# MS-PB16.net
KiCad netlist of a schematic drawn in EAGLE
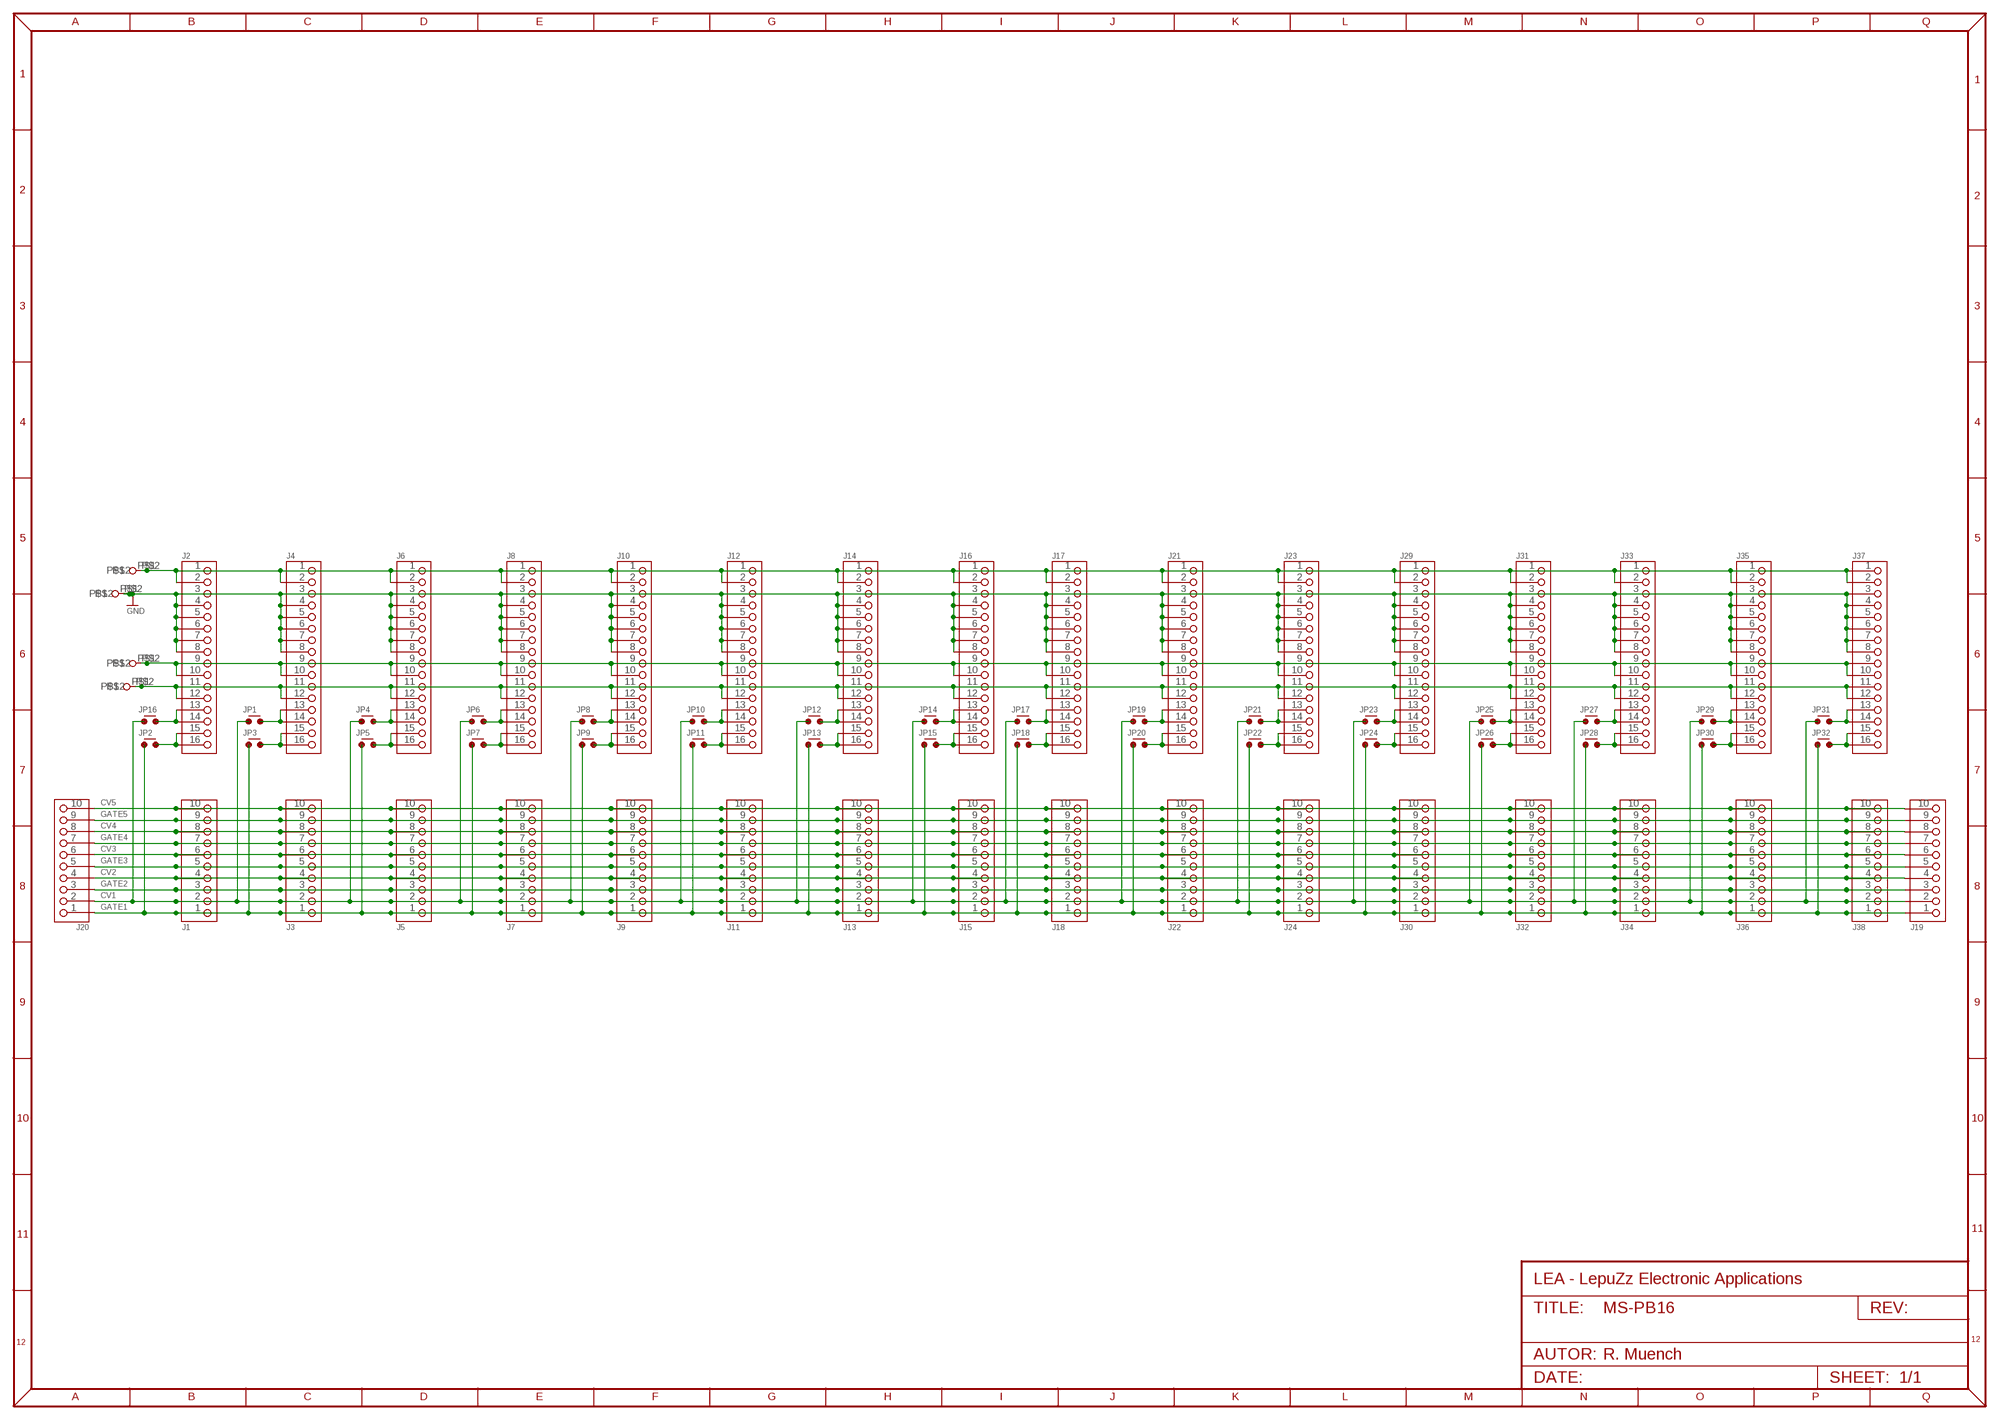
[diagram p0: schematic, sheet 1]

(export (version "E")
  (design (tool "Eeschema 10.0.6"))
  (components
    (comp (ref "J1")
      (value "CON10PD_S")
      (footprint "eagle-import:PD10S")
      (libsource (lib "eagle-import") (part "CON10PD_S"))
    )
    (comp (ref "J2")
      (value "CON16_PDS")
      (footprint "eagle-import:PD16S")
      (libsource (lib "eagle-import") (part "CON16_PDS"))
    )
    (comp (ref "J3")
      (value "CON10PD_S")
      (footprint "eagle-import:PD10S")
      (libsource (lib "eagle-import") (part "CON10PD_S"))
    )
    (comp (ref "J4")
      (value "CON16_PDS")
      (footprint "eagle-import:PD16S")
      (libsource (lib "eagle-import") (part "CON16_PDS"))
    )
    (comp (ref "J5")
      (value "CON10PD_S")
      (footprint "eagle-import:PD10S")
      (libsource (lib "eagle-import") (part "CON10PD_S"))
    )
    (comp (ref "J6")
      (value "CON16_PDS")
      (footprint "eagle-import:PD16S")
      (libsource (lib "eagle-import") (part "CON16_PDS"))
    )
    (comp (ref "J7")
      (value "CON10PD_S")
      (footprint "eagle-import:PD10S")
      (libsource (lib "eagle-import") (part "CON10PD_S"))
    )
    (comp (ref "J8")
      (value "CON16_PDS")
      (footprint "eagle-import:PD16S")
      (libsource (lib "eagle-import") (part "CON16_PDS"))
    )
    (comp (ref "J9")
      (value "CON10PD_S")
      (footprint "eagle-import:PD10S")
      (libsource (lib "eagle-import") (part "CON10PD_S"))
    )
    (comp (ref "J10")
      (value "CON16_PDS")
      (footprint "eagle-import:PD16S")
      (libsource (lib "eagle-import") (part "CON16_PDS"))
    )
    (comp (ref "J11")
      (value "CON10PD_S")
      (footprint "eagle-import:PD10S")
      (libsource (lib "eagle-import") (part "CON10PD_S"))
    )
    (comp (ref "J12")
      (value "CON16_PDS")
      (footprint "eagle-import:PD16S")
      (libsource (lib "eagle-import") (part "CON16_PDS"))
    )
    (comp (ref "J13")
      (value "CON10PD_S")
      (footprint "eagle-import:PD10S")
      (libsource (lib "eagle-import") (part "CON10PD_S"))
    )
    (comp (ref "J14")
      (value "CON16_PDS")
      (footprint "eagle-import:PD16S")
      (libsource (lib "eagle-import") (part "CON16_PDS"))
    )
    (comp (ref "J15")
      (value "CON10PD_S")
      (footprint "eagle-import:PD10S")
      (libsource (lib "eagle-import") (part "CON10PD_S"))
    )
    (comp (ref "J16")
      (value "CON16_PDS")
      (footprint "eagle-import:PD16S")
      (libsource (lib "eagle-import") (part "CON16_PDS"))
    )
    (comp (ref "J17")
      (value "CON16_PDS")
      (footprint "eagle-import:PD16S")
      (libsource (lib "eagle-import") (part "CON16_PDS"))
    )
    (comp (ref "J18")
      (value "CON10PD_S")
      (footprint "eagle-import:PD10S")
      (libsource (lib "eagle-import") (part "CON10PD_S"))
    )
    (comp (ref "J19")
      (value "CON10PD_S")
      (footprint "eagle-import:PD10S")
      (libsource (lib "eagle-import") (part "CON10PD_S"))
    )
    (comp (ref "J20")
      (value "CON10PD_S")
      (footprint "eagle-import:PD10S")
      (libsource (lib "eagle-import") (part "CON10PD_S"))
    )
    (comp (ref "J21")
      (value "CON16_PDS")
      (footprint "eagle-import:PD16S")
      (libsource (lib "eagle-import") (part "CON16_PDS"))
    )
    (comp (ref "J22")
      (value "CON10PD_S")
      (footprint "eagle-import:PD10S")
      (libsource (lib "eagle-import") (part "CON10PD_S"))
    )
    (comp (ref "J23")
      (value "CON16_PDS")
      (footprint "eagle-import:PD16S")
      (libsource (lib "eagle-import") (part "CON16_PDS"))
    )
    (comp (ref "J24")
      (value "CON10PD_S")
      (footprint "eagle-import:PD10S")
      (libsource (lib "eagle-import") (part "CON10PD_S"))
    )
    (comp (ref "J25")
      (value "FLACHSTECKER-6,35")
      (footprint "eagle-import:FLACHSTECKER-6,35")
      (libsource (lib "eagle-import") (part "FLACHSTECKER-6,35"))
    )
    (comp (ref "J26")
      (value "FLACHSTECKER-6,35")
      (footprint "eagle-import:FLACHSTECKER-6,35")
      (libsource (lib "eagle-import") (part "FLACHSTECKER-6,35"))
    )
    (comp (ref "J27")
      (value "FLACHSTECKER-6,35")
      (footprint "eagle-import:FLACHSTECKER-6,35")
      (libsource (lib "eagle-import") (part "FLACHSTECKER-6,35"))
    )
    (comp (ref "J28")
      (value "FLACHSTECKER-6,35")
      (footprint "eagle-import:FLACHSTECKER-6,35")
      (libsource (lib "eagle-import") (part "FLACHSTECKER-6,35"))
    )
    (comp (ref "J29")
      (value "CON16_PDS")
      (footprint "eagle-import:PD16S")
      (libsource (lib "eagle-import") (part "CON16_PDS"))
    )
    (comp (ref "J30")
      (value "CON10PD_S")
      (footprint "eagle-import:PD10S")
      (libsource (lib "eagle-import") (part "CON10PD_S"))
    )
    (comp (ref "J31")
      (value "CON16_PDS")
      (footprint "eagle-import:PD16S")
      (libsource (lib "eagle-import") (part "CON16_PDS"))
    )
    (comp (ref "J32")
      (value "CON10PD_S")
      (footprint "eagle-import:PD10S")
      (libsource (lib "eagle-import") (part "CON10PD_S"))
    )
    (comp (ref "J33")
      (value "CON16_PDS")
      (footprint "eagle-import:PD16S")
      (libsource (lib "eagle-import") (part "CON16_PDS"))
    )
    (comp (ref "J34")
      (value "CON10PD_S")
      (footprint "eagle-import:PD10S")
      (libsource (lib "eagle-import") (part "CON10PD_S"))
    )
    (comp (ref "J35")
      (value "CON16_PDS")
      (footprint "eagle-import:PD16S")
      (libsource (lib "eagle-import") (part "CON16_PDS"))
    )
    (comp (ref "J36")
      (value "CON10PD_S")
      (footprint "eagle-import:PD10S")
      (libsource (lib "eagle-import") (part "CON10PD_S"))
    )
    (comp (ref "J37")
      (value "CON16_PDS")
      (footprint "eagle-import:PD16S")
      (libsource (lib "eagle-import") (part "CON16_PDS"))
    )
    (comp (ref "J38")
      (value "CON10PD_S")
      (footprint "eagle-import:PD10S")
      (libsource (lib "eagle-import") (part "CON10PD_S"))
    )
    (comp (ref "JP1")
      (value "JUMP2J2")
      (footprint "eagle-import:JUMP2")
      (libsource (lib "eagle-import") (part "JUMP2J2"))
    )
    (comp (ref "JP2")
      (value "JUMP2J2")
      (footprint "eagle-import:JUMP2")
      (libsource (lib "eagle-import") (part "JUMP2J2"))
    )
    (comp (ref "JP3")
      (value "JUMP2J2")
      (footprint "eagle-import:JUMP2")
      (libsource (lib "eagle-import") (part "JUMP2J2"))
    )
    (comp (ref "JP4")
      (value "JUMP2J2")
      (footprint "eagle-import:JUMP2")
      (libsource (lib "eagle-import") (part "JUMP2J2"))
    )
    (comp (ref "JP5")
      (value "JUMP2J2")
      (footprint "eagle-import:JUMP2")
      (libsource (lib "eagle-import") (part "JUMP2J2"))
    )
    (comp (ref "JP6")
      (value "JUMP2J2")
      (footprint "eagle-import:JUMP2")
      (libsource (lib "eagle-import") (part "JUMP2J2"))
    )
    (comp (ref "JP7")
      (value "JUMP2J2")
      (footprint "eagle-import:JUMP2")
      (libsource (lib "eagle-import") (part "JUMP2J2"))
    )
    (comp (ref "JP8")
      (value "JUMP2J2")
      (footprint "eagle-import:JUMP2")
      (libsource (lib "eagle-import") (part "JUMP2J2"))
    )
    (comp (ref "JP9")
      (value "JUMP2J2")
      (footprint "eagle-import:JUMP2")
      (libsource (lib "eagle-import") (part "JUMP2J2"))
    )
    (comp (ref "JP10")
      (value "JUMP2J2")
      (footprint "eagle-import:JUMP2")
      (libsource (lib "eagle-import") (part "JUMP2J2"))
    )
    (comp (ref "JP11")
      (value "JUMP2J2")
      (footprint "eagle-import:JUMP2")
      (libsource (lib "eagle-import") (part "JUMP2J2"))
    )
    (comp (ref "JP12")
      (value "JUMP2J2")
      (footprint "eagle-import:JUMP2")
      (libsource (lib "eagle-import") (part "JUMP2J2"))
    )
    (comp (ref "JP13")
      (value "JUMP2J2")
      (footprint "eagle-import:JUMP2")
      (libsource (lib "eagle-import") (part "JUMP2J2"))
    )
    (comp (ref "JP14")
      (value "JUMP2J2")
      (footprint "eagle-import:JUMP2")
      (libsource (lib "eagle-import") (part "JUMP2J2"))
    )
    (comp (ref "JP15")
      (value "JUMP2J2")
      (footprint "eagle-import:JUMP2")
      (libsource (lib "eagle-import") (part "JUMP2J2"))
    )
    (comp (ref "JP16")
      (value "JUMP2J2")
      (footprint "eagle-import:JUMP2")
      (libsource (lib "eagle-import") (part "JUMP2J2"))
    )
    (comp (ref "JP17")
      (value "JUMP2J2")
      (footprint "eagle-import:JUMP2")
      (libsource (lib "eagle-import") (part "JUMP2J2"))
    )
    (comp (ref "JP18")
      (value "JUMP2J2")
      (footprint "eagle-import:JUMP2")
      (libsource (lib "eagle-import") (part "JUMP2J2"))
    )
    (comp (ref "JP19")
      (value "JUMP2J2")
      (footprint "eagle-import:JUMP2")
      (libsource (lib "eagle-import") (part "JUMP2J2"))
    )
    (comp (ref "JP20")
      (value "JUMP2J2")
      (footprint "eagle-import:JUMP2")
      (libsource (lib "eagle-import") (part "JUMP2J2"))
    )
    (comp (ref "JP21")
      (value "JUMP2J2")
      (footprint "eagle-import:JUMP2")
      (libsource (lib "eagle-import") (part "JUMP2J2"))
    )
    (comp (ref "JP22")
      (value "JUMP2J2")
      (footprint "eagle-import:JUMP2")
      (libsource (lib "eagle-import") (part "JUMP2J2"))
    )
    (comp (ref "JP23")
      (value "JUMP2J2")
      (footprint "eagle-import:JUMP2")
      (libsource (lib "eagle-import") (part "JUMP2J2"))
    )
    (comp (ref "JP24")
      (value "JUMP2J2")
      (footprint "eagle-import:JUMP2")
      (libsource (lib "eagle-import") (part "JUMP2J2"))
    )
    (comp (ref "JP25")
      (value "JUMP2J2")
      (footprint "eagle-import:JUMP2")
      (libsource (lib "eagle-import") (part "JUMP2J2"))
    )
    (comp (ref "JP26")
      (value "JUMP2J2")
      (footprint "eagle-import:JUMP2")
      (libsource (lib "eagle-import") (part "JUMP2J2"))
    )
    (comp (ref "JP27")
      (value "JUMP2J2")
      (footprint "eagle-import:JUMP2")
      (libsource (lib "eagle-import") (part "JUMP2J2"))
    )
    (comp (ref "JP28")
      (value "JUMP2J2")
      (footprint "eagle-import:JUMP2")
      (libsource (lib "eagle-import") (part "JUMP2J2"))
    )
    (comp (ref "JP29")
      (value "JUMP2J2")
      (footprint "eagle-import:JUMP2")
      (libsource (lib "eagle-import") (part "JUMP2J2"))
    )
    (comp (ref "JP30")
      (value "JUMP2J2")
      (footprint "eagle-import:JUMP2")
      (libsource (lib "eagle-import") (part "JUMP2J2"))
    )
    (comp (ref "JP31")
      (value "JUMP2J2")
      (footprint "eagle-import:JUMP2")
      (libsource (lib "eagle-import") (part "JUMP2J2"))
    )
    (comp (ref "JP32")
      (value "JUMP2J2")
      (footprint "eagle-import:JUMP2")
      (libsource (lib "eagle-import") (part "JUMP2J2"))
    )
  )
  (nets
    (net (code "1") (name "/+5V") (class "Default")
      (node (ref "J10") (pin "11") (pinfunction "11_11") (pintype "passive"))
      (node (ref "J10") (pin "12") (pinfunction "12_12") (pintype "passive"))
      (node (ref "J12") (pin "11") (pinfunction "11_11") (pintype "passive"))
      (node (ref "J12") (pin "12") (pinfunction "12_12") (pintype "passive"))
      (node (ref "J14") (pin "11") (pinfunction "11_11") (pintype "passive"))
      (node (ref "J14") (pin "12") (pinfunction "12_12") (pintype "passive"))
      (node (ref "J16") (pin "11") (pinfunction "11_11") (pintype "passive"))
      (node (ref "J16") (pin "12") (pinfunction "12_12") (pintype "passive"))
      (node (ref "J17") (pin "11") (pinfunction "11_11") (pintype "passive"))
      (node (ref "J17") (pin "12") (pinfunction "12_12") (pintype "passive"))
      (node (ref "J2") (pin "11") (pinfunction "11_11") (pintype "passive"))
      (node (ref "J2") (pin "12") (pinfunction "12_12") (pintype "passive"))
      (node (ref "J21") (pin "11") (pinfunction "11_11") (pintype "passive"))
      (node (ref "J21") (pin "12") (pinfunction "12_12") (pintype "passive"))
      (node (ref "J23") (pin "11") (pinfunction "11_11") (pintype "passive"))
      (node (ref "J23") (pin "12") (pinfunction "12_12") (pintype "passive"))
      (node (ref "J27") (pin "P$1") (pinfunction "P$1_P$1") (pintype "bidirectional"))
      (node (ref "J27") (pin "P$2") (pinfunction "P$2_P$2") (pintype "bidirectional"))
      (node (ref "J29") (pin "11") (pinfunction "11_11") (pintype "passive"))
      (node (ref "J29") (pin "12") (pinfunction "12_12") (pintype "passive"))
      (node (ref "J31") (pin "11") (pinfunction "11_11") (pintype "passive"))
      (node (ref "J31") (pin "12") (pinfunction "12_12") (pintype "passive"))
      (node (ref "J33") (pin "11") (pinfunction "11_11") (pintype "passive"))
      (node (ref "J33") (pin "12") (pinfunction "12_12") (pintype "passive"))
      (node (ref "J35") (pin "11") (pinfunction "11_11") (pintype "passive"))
      (node (ref "J35") (pin "12") (pinfunction "12_12") (pintype "passive"))
      (node (ref "J37") (pin "11") (pinfunction "11_11") (pintype "passive"))
      (node (ref "J37") (pin "12") (pinfunction "12_12") (pintype "passive"))
      (node (ref "J4") (pin "11") (pinfunction "11_11") (pintype "passive"))
      (node (ref "J4") (pin "12") (pinfunction "12_12") (pintype "passive"))
      (node (ref "J6") (pin "11") (pinfunction "11_11") (pintype "passive"))
      (node (ref "J6") (pin "12") (pinfunction "12_12") (pintype "passive"))
      (node (ref "J8") (pin "11") (pinfunction "11_11") (pintype "passive"))
      (node (ref "J8") (pin "12") (pinfunction "12_12") (pintype "passive"))
    )
    (net (code "2") (name "/+12V") (class "Default")
      (node (ref "J10") (pin "10") (pinfunction "10_10") (pintype "passive"))
      (node (ref "J10") (pin "9") (pinfunction "9_9") (pintype "passive"))
      (node (ref "J12") (pin "10") (pinfunction "10_10") (pintype "passive"))
      (node (ref "J12") (pin "9") (pinfunction "9_9") (pintype "passive"))
      (node (ref "J14") (pin "10") (pinfunction "10_10") (pintype "passive"))
      (node (ref "J14") (pin "9") (pinfunction "9_9") (pintype "passive"))
      (node (ref "J16") (pin "10") (pinfunction "10_10") (pintype "passive"))
      (node (ref "J16") (pin "9") (pinfunction "9_9") (pintype "passive"))
      (node (ref "J17") (pin "10") (pinfunction "10_10") (pintype "passive"))
      (node (ref "J17") (pin "9") (pinfunction "9_9") (pintype "passive"))
      (node (ref "J2") (pin "10") (pinfunction "10_10") (pintype "passive"))
      (node (ref "J2") (pin "9") (pinfunction "9_9") (pintype "passive"))
      (node (ref "J21") (pin "10") (pinfunction "10_10") (pintype "passive"))
      (node (ref "J21") (pin "9") (pinfunction "9_9") (pintype "passive"))
      (node (ref "J23") (pin "10") (pinfunction "10_10") (pintype "passive"))
      (node (ref "J23") (pin "9") (pinfunction "9_9") (pintype "passive"))
      (node (ref "J26") (pin "P$1") (pinfunction "P$1_P$1") (pintype "bidirectional"))
      (node (ref "J26") (pin "P$2") (pinfunction "P$2_P$2") (pintype "bidirectional"))
      (node (ref "J29") (pin "10") (pinfunction "10_10") (pintype "passive"))
      (node (ref "J29") (pin "9") (pinfunction "9_9") (pintype "passive"))
      (node (ref "J31") (pin "10") (pinfunction "10_10") (pintype "passive"))
      (node (ref "J31") (pin "9") (pinfunction "9_9") (pintype "passive"))
      (node (ref "J33") (pin "10") (pinfunction "10_10") (pintype "passive"))
      (node (ref "J33") (pin "9") (pinfunction "9_9") (pintype "passive"))
      (node (ref "J35") (pin "10") (pinfunction "10_10") (pintype "passive"))
      (node (ref "J35") (pin "9") (pinfunction "9_9") (pintype "passive"))
      (node (ref "J37") (pin "10") (pinfunction "10_10") (pintype "passive"))
      (node (ref "J37") (pin "9") (pinfunction "9_9") (pintype "passive"))
      (node (ref "J4") (pin "10") (pinfunction "10_10") (pintype "passive"))
      (node (ref "J4") (pin "9") (pinfunction "9_9") (pintype "passive"))
      (node (ref "J6") (pin "10") (pinfunction "10_10") (pintype "passive"))
      (node (ref "J6") (pin "9") (pinfunction "9_9") (pintype "passive"))
      (node (ref "J8") (pin "10") (pinfunction "10_10") (pintype "passive"))
      (node (ref "J8") (pin "9") (pinfunction "9_9") (pintype "passive"))
    )
    (net (code "3") (name "/-12V") (class "Default")
      (node (ref "J10") (pin "1") (pinfunction "1_1") (pintype "passive"))
      (node (ref "J10") (pin "2") (pinfunction "2_2") (pintype "passive"))
      (node (ref "J12") (pin "1") (pinfunction "1_1") (pintype "passive"))
      (node (ref "J12") (pin "2") (pinfunction "2_2") (pintype "passive"))
      (node (ref "J14") (pin "1") (pinfunction "1_1") (pintype "passive"))
      (node (ref "J14") (pin "2") (pinfunction "2_2") (pintype "passive"))
      (node (ref "J16") (pin "1") (pinfunction "1_1") (pintype "passive"))
      (node (ref "J16") (pin "2") (pinfunction "2_2") (pintype "passive"))
      (node (ref "J17") (pin "1") (pinfunction "1_1") (pintype "passive"))
      (node (ref "J17") (pin "2") (pinfunction "2_2") (pintype "passive"))
      (node (ref "J2") (pin "1") (pinfunction "1_1") (pintype "passive"))
      (node (ref "J2") (pin "2") (pinfunction "2_2") (pintype "passive"))
      (node (ref "J21") (pin "1") (pinfunction "1_1") (pintype "passive"))
      (node (ref "J21") (pin "2") (pinfunction "2_2") (pintype "passive"))
      (node (ref "J23") (pin "1") (pinfunction "1_1") (pintype "passive"))
      (node (ref "J23") (pin "2") (pinfunction "2_2") (pintype "passive"))
      (node (ref "J25") (pin "P$1") (pinfunction "P$1_P$1") (pintype "bidirectional"))
      (node (ref "J25") (pin "P$2") (pinfunction "P$2_P$2") (pintype "bidirectional"))
      (node (ref "J29") (pin "1") (pinfunction "1_1") (pintype "passive"))
      (node (ref "J29") (pin "2") (pinfunction "2_2") (pintype "passive"))
      (node (ref "J31") (pin "1") (pinfunction "1_1") (pintype "passive"))
      (node (ref "J31") (pin "2") (pinfunction "2_2") (pintype "passive"))
      (node (ref "J33") (pin "1") (pinfunction "1_1") (pintype "passive"))
      (node (ref "J33") (pin "2") (pinfunction "2_2") (pintype "passive"))
      (node (ref "J35") (pin "1") (pinfunction "1_1") (pintype "passive"))
      (node (ref "J35") (pin "2") (pinfunction "2_2") (pintype "passive"))
      (node (ref "J37") (pin "1") (pinfunction "1_1") (pintype "passive"))
      (node (ref "J37") (pin "2") (pinfunction "2_2") (pintype "passive"))
      (node (ref "J4") (pin "1") (pinfunction "1_1") (pintype "passive"))
      (node (ref "J4") (pin "2") (pinfunction "2_2") (pintype "passive"))
      (node (ref "J6") (pin "1") (pinfunction "1_1") (pintype "passive"))
      (node (ref "J6") (pin "2") (pinfunction "2_2") (pintype "passive"))
      (node (ref "J8") (pin "1") (pinfunction "1_1") (pintype "passive"))
      (node (ref "J8") (pin "2") (pinfunction "2_2") (pintype "passive"))
    )
    (net (code "4") (name "/CV1") (class "Default")
      (node (ref "J1") (pin "2") (pinfunction "2_2") (pintype "passive"))
      (node (ref "J11") (pin "2") (pinfunction "2_2") (pintype "passive"))
      (node (ref "J13") (pin "2") (pinfunction "2_2") (pintype "passive"))
      (node (ref "J15") (pin "2") (pinfunction "2_2") (pintype "passive"))
      (node (ref "J18") (pin "2") (pinfunction "2_2") (pintype "passive"))
      (node (ref "J19") (pin "2") (pinfunction "2_2") (pintype "passive"))
      (node (ref "J20") (pin "2") (pinfunction "2_2") (pintype "passive"))
      (node (ref "J22") (pin "2") (pinfunction "2_2") (pintype "passive"))
      (node (ref "J24") (pin "2") (pinfunction "2_2") (pintype "passive"))
      (node (ref "J3") (pin "2") (pinfunction "2_2") (pintype "passive"))
      (node (ref "J30") (pin "2") (pinfunction "2_2") (pintype "passive"))
      (node (ref "J32") (pin "2") (pinfunction "2_2") (pintype "passive"))
      (node (ref "J34") (pin "2") (pinfunction "2_2") (pintype "passive"))
      (node (ref "J36") (pin "2") (pinfunction "2_2") (pintype "passive"))
      (node (ref "J38") (pin "2") (pinfunction "2_2") (pintype "passive"))
      (node (ref "J5") (pin "2") (pinfunction "2_2") (pintype "passive"))
      (node (ref "J7") (pin "2") (pinfunction "2_2") (pintype "passive"))
      (node (ref "J9") (pin "2") (pinfunction "2_2") (pintype "passive"))
      (node (ref "JP1") (pin "1") (pinfunction "1_1") (pintype "passive"))
      (node (ref "JP10") (pin "1") (pinfunction "1_1") (pintype "passive"))
      (node (ref "JP12") (pin "1") (pinfunction "1_1") (pintype "passive"))
      (node (ref "JP14") (pin "1") (pinfunction "1_1") (pintype "passive"))
      (node (ref "JP16") (pin "1") (pinfunction "1_1") (pintype "passive"))
      (node (ref "JP17") (pin "1") (pinfunction "1_1") (pintype "passive"))
      (node (ref "JP19") (pin "1") (pinfunction "1_1") (pintype "passive"))
      (node (ref "JP21") (pin "1") (pinfunction "1_1") (pintype "passive"))
      (node (ref "JP23") (pin "1") (pinfunction "1_1") (pintype "passive"))
      (node (ref "JP25") (pin "1") (pinfunction "1_1") (pintype "passive"))
      (node (ref "JP27") (pin "1") (pinfunction "1_1") (pintype "passive"))
      (node (ref "JP29") (pin "1") (pinfunction "1_1") (pintype "passive"))
      (node (ref "JP31") (pin "1") (pinfunction "1_1") (pintype "passive"))
      (node (ref "JP4") (pin "1") (pinfunction "1_1") (pintype "passive"))
      (node (ref "JP6") (pin "1") (pinfunction "1_1") (pintype "passive"))
      (node (ref "JP8") (pin "1") (pinfunction "1_1") (pintype "passive"))
    )
    (net (code "5") (name "/CV2") (class "Default")
      (node (ref "J1") (pin "4") (pinfunction "4_4") (pintype "passive"))
      (node (ref "J11") (pin "4") (pinfunction "4_4") (pintype "passive"))
      (node (ref "J13") (pin "4") (pinfunction "4_4") (pintype "passive"))
      (node (ref "J15") (pin "4") (pinfunction "4_4") (pintype "passive"))
      (node (ref "J18") (pin "4") (pinfunction "4_4") (pintype "passive"))
      (node (ref "J19") (pin "4") (pinfunction "4_4") (pintype "passive"))
      (node (ref "J20") (pin "4") (pinfunction "4_4") (pintype "passive"))
      (node (ref "J22") (pin "4") (pinfunction "4_4") (pintype "passive"))
      (node (ref "J24") (pin "4") (pinfunction "4_4") (pintype "passive"))
      (node (ref "J3") (pin "4") (pinfunction "4_4") (pintype "passive"))
      (node (ref "J30") (pin "4") (pinfunction "4_4") (pintype "passive"))
      (node (ref "J32") (pin "4") (pinfunction "4_4") (pintype "passive"))
      (node (ref "J34") (pin "4") (pinfunction "4_4") (pintype "passive"))
      (node (ref "J36") (pin "4") (pinfunction "4_4") (pintype "passive"))
      (node (ref "J38") (pin "4") (pinfunction "4_4") (pintype "passive"))
      (node (ref "J5") (pin "4") (pinfunction "4_4") (pintype "passive"))
      (node (ref "J7") (pin "4") (pinfunction "4_4") (pintype "passive"))
      (node (ref "J9") (pin "4") (pinfunction "4_4") (pintype "passive"))
    )
    (net (code "6") (name "/CV3") (class "Default")
      (node (ref "J1") (pin "6") (pinfunction "6_6") (pintype "passive"))
      (node (ref "J11") (pin "6") (pinfunction "6_6") (pintype "passive"))
      (node (ref "J13") (pin "6") (pinfunction "6_6") (pintype "passive"))
      (node (ref "J15") (pin "6") (pinfunction "6_6") (pintype "passive"))
      (node (ref "J18") (pin "6") (pinfunction "6_6") (pintype "passive"))
      (node (ref "J19") (pin "6") (pinfunction "6_6") (pintype "passive"))
      (node (ref "J20") (pin "6") (pinfunction "6_6") (pintype "passive"))
      (node (ref "J22") (pin "6") (pinfunction "6_6") (pintype "passive"))
      (node (ref "J24") (pin "6") (pinfunction "6_6") (pintype "passive"))
      (node (ref "J3") (pin "6") (pinfunction "6_6") (pintype "passive"))
      (node (ref "J30") (pin "6") (pinfunction "6_6") (pintype "passive"))
      (node (ref "J32") (pin "6") (pinfunction "6_6") (pintype "passive"))
      (node (ref "J34") (pin "6") (pinfunction "6_6") (pintype "passive"))
      (node (ref "J36") (pin "6") (pinfunction "6_6") (pintype "passive"))
      (node (ref "J38") (pin "6") (pinfunction "6_6") (pintype "passive"))
      (node (ref "J5") (pin "6") (pinfunction "6_6") (pintype "passive"))
      (node (ref "J7") (pin "6") (pinfunction "6_6") (pintype "passive"))
      (node (ref "J9") (pin "6") (pinfunction "6_6") (pintype "passive"))
    )
    (net (code "7") (name "/CV4") (class "Default")
      (node (ref "J1") (pin "8") (pinfunction "8_8") (pintype "passive"))
      (node (ref "J11") (pin "8") (pinfunction "8_8") (pintype "passive"))
      (node (ref "J13") (pin "8") (pinfunction "8_8") (pintype "passive"))
      (node (ref "J15") (pin "8") (pinfunction "8_8") (pintype "passive"))
      (node (ref "J18") (pin "8") (pinfunction "8_8") (pintype "passive"))
      (node (ref "J19") (pin "8") (pinfunction "8_8") (pintype "passive"))
      (node (ref "J20") (pin "8") (pinfunction "8_8") (pintype "passive"))
      (node (ref "J22") (pin "8") (pinfunction "8_8") (pintype "passive"))
      (node (ref "J24") (pin "8") (pinfunction "8_8") (pintype "passive"))
      (node (ref "J3") (pin "8") (pinfunction "8_8") (pintype "passive"))
      (node (ref "J30") (pin "8") (pinfunction "8_8") (pintype "passive"))
      (node (ref "J32") (pin "8") (pinfunction "8_8") (pintype "passive"))
      (node (ref "J34") (pin "8") (pinfunction "8_8") (pintype "passive"))
      (node (ref "J36") (pin "8") (pinfunction "8_8") (pintype "passive"))
      (node (ref "J38") (pin "8") (pinfunction "8_8") (pintype "passive"))
      (node (ref "J5") (pin "8") (pinfunction "8_8") (pintype "passive"))
      (node (ref "J7") (pin "8") (pinfunction "8_8") (pintype "passive"))
      (node (ref "J9") (pin "8") (pinfunction "8_8") (pintype "passive"))
    )
    (net (code "8") (name "/CV5") (class "Default")
      (node (ref "J1") (pin "10") (pinfunction "10_10") (pintype "passive"))
      (node (ref "J11") (pin "10") (pinfunction "10_10") (pintype "passive"))
      (node (ref "J13") (pin "10") (pinfunction "10_10") (pintype "passive"))
      (node (ref "J15") (pin "10") (pinfunction "10_10") (pintype "passive"))
      (node (ref "J18") (pin "10") (pinfunction "10_10") (pintype "passive"))
      (node (ref "J19") (pin "10") (pinfunction "10_10") (pintype "passive"))
      (node (ref "J20") (pin "10") (pinfunction "10_10") (pintype "passive"))
      (node (ref "J22") (pin "10") (pinfunction "10_10") (pintype "passive"))
      (node (ref "J24") (pin "10") (pinfunction "10_10") (pintype "passive"))
      (node (ref "J3") (pin "10") (pinfunction "10_10") (pintype "passive"))
      (node (ref "J30") (pin "10") (pinfunction "10_10") (pintype "passive"))
      (node (ref "J32") (pin "10") (pinfunction "10_10") (pintype "passive"))
      (node (ref "J34") (pin "10") (pinfunction "10_10") (pintype "passive"))
      (node (ref "J36") (pin "10") (pinfunction "10_10") (pintype "passive"))
      (node (ref "J38") (pin "10") (pinfunction "10_10") (pintype "passive"))
      (node (ref "J5") (pin "10") (pinfunction "10_10") (pintype "passive"))
      (node (ref "J7") (pin "10") (pinfunction "10_10") (pintype "passive"))
      (node (ref "J9") (pin "10") (pinfunction "10_10") (pintype "passive"))
    )
    (net (code "9") (name "/GATE1") (class "Default")
      (node (ref "J1") (pin "1") (pinfunction "1_1") (pintype "passive"))
      (node (ref "J11") (pin "1") (pinfunction "1_1") (pintype "passive"))
      (node (ref "J13") (pin "1") (pinfunction "1_1") (pintype "passive"))
      (node (ref "J15") (pin "1") (pinfunction "1_1") (pintype "passive"))
      (node (ref "J18") (pin "1") (pinfunction "1_1") (pintype "passive"))
      (node (ref "J19") (pin "1") (pinfunction "1_1") (pintype "passive"))
      (node (ref "J20") (pin "1") (pinfunction "1_1") (pintype "passive"))
      (node (ref "J22") (pin "1") (pinfunction "1_1") (pintype "passive"))
      (node (ref "J24") (pin "1") (pinfunction "1_1") (pintype "passive"))
      (node (ref "J3") (pin "1") (pinfunction "1_1") (pintype "passive"))
      (node (ref "J30") (pin "1") (pinfunction "1_1") (pintype "passive"))
      (node (ref "J32") (pin "1") (pinfunction "1_1") (pintype "passive"))
      (node (ref "J34") (pin "1") (pinfunction "1_1") (pintype "passive"))
      (node (ref "J36") (pin "1") (pinfunction "1_1") (pintype "passive"))
      (node (ref "J38") (pin "1") (pinfunction "1_1") (pintype "passive"))
      (node (ref "J5") (pin "1") (pinfunction "1_1") (pintype "passive"))
      (node (ref "J7") (pin "1") (pinfunction "1_1") (pintype "passive"))
      (node (ref "J9") (pin "1") (pinfunction "1_1") (pintype "passive"))
      (node (ref "JP11") (pin "1") (pinfunction "1_1") (pintype "passive"))
      (node (ref "JP13") (pin "1") (pinfunction "1_1") (pintype "passive"))
      (node (ref "JP15") (pin "1") (pinfunction "1_1") (pintype "passive"))
      (node (ref "JP18") (pin "1") (pinfunction "1_1") (pintype "passive"))
      (node (ref "JP2") (pin "1") (pinfunction "1_1") (pintype "passive"))
      (node (ref "JP20") (pin "1") (pinfunction "1_1") (pintype "passive"))
      (node (ref "JP22") (pin "1") (pinfunction "1_1") (pintype "passive"))
      (node (ref "JP24") (pin "1") (pinfunction "1_1") (pintype "passive"))
      (node (ref "JP26") (pin "1") (pinfunction "1_1") (pintype "passive"))
      (node (ref "JP28") (pin "1") (pinfunction "1_1") (pintype "passive"))
      (node (ref "JP3") (pin "1") (pinfunction "1_1") (pintype "passive"))
      (node (ref "JP30") (pin "1") (pinfunction "1_1") (pintype "passive"))
      (node (ref "JP32") (pin "1") (pinfunction "1_1") (pintype "passive"))
      (node (ref "JP5") (pin "1") (pinfunction "1_1") (pintype "passive"))
      (node (ref "JP7") (pin "1") (pinfunction "1_1") (pintype "passive"))
      (node (ref "JP9") (pin "1") (pinfunction "1_1") (pintype "passive"))
    )
    (net (code "10") (name "/GATE2") (class "Default")
      (node (ref "J1") (pin "3") (pinfunction "3_3") (pintype "passive"))
      (node (ref "J11") (pin "3") (pinfunction "3_3") (pintype "passive"))
      (node (ref "J13") (pin "3") (pinfunction "3_3") (pintype "passive"))
      (node (ref "J15") (pin "3") (pinfunction "3_3") (pintype "passive"))
      (node (ref "J18") (pin "3") (pinfunction "3_3") (pintype "passive"))
      (node (ref "J19") (pin "3") (pinfunction "3_3") (pintype "passive"))
      (node (ref "J20") (pin "3") (pinfunction "3_3") (pintype "passive"))
      (node (ref "J22") (pin "3") (pinfunction "3_3") (pintype "passive"))
      (node (ref "J24") (pin "3") (pinfunction "3_3") (pintype "passive"))
      (node (ref "J3") (pin "3") (pinfunction "3_3") (pintype "passive"))
      (node (ref "J30") (pin "3") (pinfunction "3_3") (pintype "passive"))
      (node (ref "J32") (pin "3") (pinfunction "3_3") (pintype "passive"))
      (node (ref "J34") (pin "3") (pinfunction "3_3") (pintype "passive"))
      (node (ref "J36") (pin "3") (pinfunction "3_3") (pintype "passive"))
      (node (ref "J38") (pin "3") (pinfunction "3_3") (pintype "passive"))
      (node (ref "J5") (pin "3") (pinfunction "3_3") (pintype "passive"))
      (node (ref "J7") (pin "3") (pinfunction "3_3") (pintype "passive"))
      (node (ref "J9") (pin "3") (pinfunction "3_3") (pintype "passive"))
    )
    (net (code "11") (name "/GATE3") (class "Default")
      (node (ref "J1") (pin "5") (pinfunction "5_5") (pintype "passive"))
      (node (ref "J11") (pin "5") (pinfunction "5_5") (pintype "passive"))
      (node (ref "J13") (pin "5") (pinfunction "5_5") (pintype "passive"))
      (node (ref "J15") (pin "5") (pinfunction "5_5") (pintype "passive"))
      (node (ref "J18") (pin "5") (pinfunction "5_5") (pintype "passive"))
      (node (ref "J19") (pin "5") (pinfunction "5_5") (pintype "passive"))
      (node (ref "J20") (pin "5") (pinfunction "5_5") (pintype "passive"))
      (node (ref "J22") (pin "5") (pinfunction "5_5") (pintype "passive"))
      (node (ref "J24") (pin "5") (pinfunction "5_5") (pintype "passive"))
      (node (ref "J3") (pin "5") (pinfunction "5_5") (pintype "passive"))
      (node (ref "J30") (pin "5") (pinfunction "5_5") (pintype "passive"))
      (node (ref "J32") (pin "5") (pinfunction "5_5") (pintype "passive"))
      (node (ref "J34") (pin "5") (pinfunction "5_5") (pintype "passive"))
      (node (ref "J36") (pin "5") (pinfunction "5_5") (pintype "passive"))
      (node (ref "J38") (pin "5") (pinfunction "5_5") (pintype "passive"))
      (node (ref "J5") (pin "5") (pinfunction "5_5") (pintype "passive"))
      (node (ref "J7") (pin "5") (pinfunction "5_5") (pintype "passive"))
      (node (ref "J9") (pin "5") (pinfunction "5_5") (pintype "passive"))
    )
    (net (code "12") (name "/GATE4") (class "Default")
      (node (ref "J1") (pin "7") (pinfunction "7_7") (pintype "passive"))
      (node (ref "J11") (pin "7") (pinfunction "7_7") (pintype "passive"))
      (node (ref "J13") (pin "7") (pinfunction "7_7") (pintype "passive"))
      (node (ref "J15") (pin "7") (pinfunction "7_7") (pintype "passive"))
      (node (ref "J18") (pin "7") (pinfunction "7_7") (pintype "passive"))
      (node (ref "J19") (pin "7") (pinfunction "7_7") (pintype "passive"))
      (node (ref "J20") (pin "7") (pinfunction "7_7") (pintype "passive"))
      (node (ref "J22") (pin "7") (pinfunction "7_7") (pintype "passive"))
      (node (ref "J24") (pin "7") (pinfunction "7_7") (pintype "passive"))
      (node (ref "J3") (pin "7") (pinfunction "7_7") (pintype "passive"))
      (node (ref "J30") (pin "7") (pinfunction "7_7") (pintype "passive"))
      (node (ref "J32") (pin "7") (pinfunction "7_7") (pintype "passive"))
      (node (ref "J34") (pin "7") (pinfunction "7_7") (pintype "passive"))
      (node (ref "J36") (pin "7") (pinfunction "7_7") (pintype "passive"))
      (node (ref "J38") (pin "7") (pinfunction "7_7") (pintype "passive"))
      (node (ref "J5") (pin "7") (pinfunction "7_7") (pintype "passive"))
      (node (ref "J7") (pin "7") (pinfunction "7_7") (pintype "passive"))
      (node (ref "J9") (pin "7") (pinfunction "7_7") (pintype "passive"))
    )
    (net (code "13") (name "/GATE5") (class "Default")
      (node (ref "J1") (pin "9") (pinfunction "9_9") (pintype "passive"))
      (node (ref "J11") (pin "9") (pinfunction "9_9") (pintype "passive"))
      (node (ref "J13") (pin "9") (pinfunction "9_9") (pintype "passive"))
      (node (ref "J15") (pin "9") (pinfunction "9_9") (pintype "passive"))
      (node (ref "J18") (pin "9") (pinfunction "9_9") (pintype "passive"))
      (node (ref "J19") (pin "9") (pinfunction "9_9") (pintype "passive"))
      (node (ref "J20") (pin "9") (pinfunction "9_9") (pintype "passive"))
      (node (ref "J22") (pin "9") (pinfunction "9_9") (pintype "passive"))
      (node (ref "J24") (pin "9") (pinfunction "9_9") (pintype "passive"))
      (node (ref "J3") (pin "9") (pinfunction "9_9") (pintype "passive"))
      (node (ref "J30") (pin "9") (pinfunction "9_9") (pintype "passive"))
      (node (ref "J32") (pin "9") (pinfunction "9_9") (pintype "passive"))
      (node (ref "J34") (pin "9") (pinfunction "9_9") (pintype "passive"))
      (node (ref "J36") (pin "9") (pinfunction "9_9") (pintype "passive"))
      (node (ref "J38") (pin "9") (pinfunction "9_9") (pintype "passive"))
      (node (ref "J5") (pin "9") (pinfunction "9_9") (pintype "passive"))
      (node (ref "J7") (pin "9") (pinfunction "9_9") (pintype "passive"))
      (node (ref "J9") (pin "9") (pinfunction "9_9") (pintype "passive"))
    )
    (net (code "14") (name "GND") (class "Default")
      (node (ref "J10") (pin "3") (pinfunction "3_3") (pintype "passive"))
      (node (ref "J10") (pin "4") (pinfunction "4_4") (pintype "passive"))
      (node (ref "J10") (pin "5") (pinfunction "5_5") (pintype "passive"))
      (node (ref "J10") (pin "6") (pinfunction "6_6") (pintype "passive"))
      (node (ref "J10") (pin "7") (pinfunction "7_7") (pintype "passive"))
      (node (ref "J10") (pin "8") (pinfunction "8_8") (pintype "passive"))
      (node (ref "J12") (pin "3") (pinfunction "3_3") (pintype "passive"))
      (node (ref "J12") (pin "4") (pinfunction "4_4") (pintype "passive"))
      (node (ref "J12") (pin "5") (pinfunction "5_5") (pintype "passive"))
      (node (ref "J12") (pin "6") (pinfunction "6_6") (pintype "passive"))
      (node (ref "J12") (pin "7") (pinfunction "7_7") (pintype "passive"))
      (node (ref "J12") (pin "8") (pinfunction "8_8") (pintype "passive"))
      (node (ref "J14") (pin "3") (pinfunction "3_3") (pintype "passive"))
      (node (ref "J14") (pin "4") (pinfunction "4_4") (pintype "passive"))
      (node (ref "J14") (pin "5") (pinfunction "5_5") (pintype "passive"))
      (node (ref "J14") (pin "6") (pinfunction "6_6") (pintype "passive"))
      (node (ref "J14") (pin "7") (pinfunction "7_7") (pintype "passive"))
      (node (ref "J14") (pin "8") (pinfunction "8_8") (pintype "passive"))
      (node (ref "J16") (pin "3") (pinfunction "3_3") (pintype "passive"))
      (node (ref "J16") (pin "4") (pinfunction "4_4") (pintype "passive"))
      (node (ref "J16") (pin "5") (pinfunction "5_5") (pintype "passive"))
      (node (ref "J16") (pin "6") (pinfunction "6_6") (pintype "passive"))
      (node (ref "J16") (pin "7") (pinfunction "7_7") (pintype "passive"))
      (node (ref "J16") (pin "8") (pinfunction "8_8") (pintype "passive"))
      (node (ref "J17") (pin "3") (pinfunction "3_3") (pintype "passive"))
      (node (ref "J17") (pin "4") (pinfunction "4_4") (pintype "passive"))
      (node (ref "J17") (pin "5") (pinfunction "5_5") (pintype "passive"))
      (node (ref "J17") (pin "6") (pinfunction "6_6") (pintype "passive"))
      (node (ref "J17") (pin "7") (pinfunction "7_7") (pintype "passive"))
      (node (ref "J17") (pin "8") (pinfunction "8_8") (pintype "passive"))
      (node (ref "J2") (pin "3") (pinfunction "3_3") (pintype "passive"))
      (node (ref "J2") (pin "4") (pinfunction "4_4") (pintype "passive"))
      (node (ref "J2") (pin "5") (pinfunction "5_5") (pintype "passive"))
      (node (ref "J2") (pin "6") (pinfunction "6_6") (pintype "passive"))
      (node (ref "J2") (pin "7") (pinfunction "7_7") (pintype "passive"))
      (node (ref "J2") (pin "8") (pinfunction "8_8") (pintype "passive"))
      (node (ref "J21") (pin "3") (pinfunction "3_3") (pintype "passive"))
      (node (ref "J21") (pin "4") (pinfunction "4_4") (pintype "passive"))
      (node (ref "J21") (pin "5") (pinfunction "5_5") (pintype "passive"))
      (node (ref "J21") (pin "6") (pinfunction "6_6") (pintype "passive"))
      (node (ref "J21") (pin "7") (pinfunction "7_7") (pintype "passive"))
      (node (ref "J21") (pin "8") (pinfunction "8_8") (pintype "passive"))
      (node (ref "J23") (pin "3") (pinfunction "3_3") (pintype "passive"))
      (node (ref "J23") (pin "4") (pinfunction "4_4") (pintype "passive"))
      (node (ref "J23") (pin "5") (pinfunction "5_5") (pintype "passive"))
      (node (ref "J23") (pin "6") (pinfunction "6_6") (pintype "passive"))
      (node (ref "J23") (pin "7") (pinfunction "7_7") (pintype "passive"))
      (node (ref "J23") (pin "8") (pinfunction "8_8") (pintype "passive"))
      (node (ref "J28") (pin "P$1") (pinfunction "P$1_P$1") (pintype "bidirectional"))
      (node (ref "J28") (pin "P$2") (pinfunction "P$2_P$2") (pintype "bidirectional"))
      (node (ref "J29") (pin "3") (pinfunction "3_3") (pintype "passive"))
      (node (ref "J29") (pin "4") (pinfunction "4_4") (pintype "passive"))
      (node (ref "J29") (pin "5") (pinfunction "5_5") (pintype "passive"))
      (node (ref "J29") (pin "6") (pinfunction "6_6") (pintype "passive"))
      (node (ref "J29") (pin "7") (pinfunction "7_7") (pintype "passive"))
      (node (ref "J29") (pin "8") (pinfunction "8_8") (pintype "passive"))
      (node (ref "J31") (pin "3") (pinfunction "3_3") (pintype "passive"))
      (node (ref "J31") (pin "4") (pinfunction "4_4") (pintype "passive"))
      (node (ref "J31") (pin "5") (pinfunction "5_5") (pintype "passive"))
      (node (ref "J31") (pin "6") (pinfunction "6_6") (pintype "passive"))
      (node (ref "J31") (pin "7") (pinfunction "7_7") (pintype "passive"))
      (node (ref "J31") (pin "8") (pinfunction "8_8") (pintype "passive"))
      (node (ref "J33") (pin "3") (pinfunction "3_3") (pintype "passive"))
      (node (ref "J33") (pin "4") (pinfunction "4_4") (pintype "passive"))
      (node (ref "J33") (pin "5") (pinfunction "5_5") (pintype "passive"))
      (node (ref "J33") (pin "6") (pinfunction "6_6") (pintype "passive"))
      (node (ref "J33") (pin "7") (pinfunction "7_7") (pintype "passive"))
      (node (ref "J33") (pin "8") (pinfunction "8_8") (pintype "passive"))
      (node (ref "J35") (pin "3") (pinfunction "3_3") (pintype "passive"))
      (node (ref "J35") (pin "4") (pinfunction "4_4") (pintype "passive"))
      (node (ref "J35") (pin "5") (pinfunction "5_5") (pintype "passive"))
      (node (ref "J35") (pin "6") (pinfunction "6_6") (pintype "passive"))
      (node (ref "J35") (pin "7") (pinfunction "7_7") (pintype "passive"))
      (node (ref "J35") (pin "8") (pinfunction "8_8") (pintype "passive"))
      (node (ref "J37") (pin "3") (pinfunction "3_3") (pintype "passive"))
      (node (ref "J37") (pin "4") (pinfunction "4_4") (pintype "passive"))
      (node (ref "J37") (pin "5") (pinfunction "5_5") (pintype "passive"))
      (node (ref "J37") (pin "6") (pinfunction "6_6") (pintype "passive"))
      (node (ref "J37") (pin "7") (pinfunction "7_7") (pintype "passive"))
      (node (ref "J37") (pin "8") (pinfunction "8_8") (pintype "passive"))
      (node (ref "J4") (pin "3") (pinfunction "3_3") (pintype "passive"))
      (node (ref "J4") (pin "4") (pinfunction "4_4") (pintype "passive"))
      (node (ref "J4") (pin "5") (pinfunction "5_5") (pintype "passive"))
      (node (ref "J4") (pin "6") (pinfunction "6_6") (pintype "passive"))
      (node (ref "J4") (pin "7") (pinfunction "7_7") (pintype "passive"))
      (node (ref "J4") (pin "8") (pinfunction "8_8") (pintype "passive"))
      (node (ref "J6") (pin "3") (pinfunction "3_3") (pintype "passive"))
      (node (ref "J6") (pin "4") (pinfunction "4_4") (pintype "passive"))
      (node (ref "J6") (pin "5") (pinfunction "5_5") (pintype "passive"))
      (node (ref "J6") (pin "6") (pinfunction "6_6") (pintype "passive"))
      (node (ref "J6") (pin "7") (pinfunction "7_7") (pintype "passive"))
      (node (ref "J6") (pin "8") (pinfunction "8_8") (pintype "passive"))
      (node (ref "J8") (pin "3") (pinfunction "3_3") (pintype "passive"))
      (node (ref "J8") (pin "4") (pinfunction "4_4") (pintype "passive"))
      (node (ref "J8") (pin "5") (pinfunction "5_5") (pintype "passive"))
      (node (ref "J8") (pin "6") (pinfunction "6_6") (pintype "passive"))
      (node (ref "J8") (pin "7") (pinfunction "7_7") (pintype "passive"))
      (node (ref "J8") (pin "8") (pinfunction "8_8") (pintype "passive"))
    )
    (net (code "15") (name "Net-(J2-Pad13)") (class "Default")
      (node (ref "J2") (pin "13") (pinfunction "13_13") (pintype "passive"))
      (node (ref "J2") (pin "14") (pinfunction "14_14") (pintype "passive"))
      (node (ref "JP16") (pin "2") (pinfunction "2_2") (pintype "passive"))
    )
    (net (code "16") (name "Net-(J2-Pad15)") (class "Default")
      (node (ref "J2") (pin "15") (pinfunction "15_15") (pintype "passive"))
      (node (ref "J2") (pin "16") (pinfunction "16_16") (pintype "passive"))
      (node (ref "JP2") (pin "2") (pinfunction "2_2") (pintype "passive"))
    )
    (net (code "17") (name "Net-(J4-Pad13)") (class "Default")
      (node (ref "J4") (pin "13") (pinfunction "13_13") (pintype "passive"))
      (node (ref "J4") (pin "14") (pinfunction "14_14") (pintype "passive"))
      (node (ref "JP1") (pin "2") (pinfunction "2_2") (pintype "passive"))
    )
    (net (code "18") (name "Net-(J4-Pad15)") (class "Default")
      (node (ref "J4") (pin "15") (pinfunction "15_15") (pintype "passive"))
      (node (ref "J4") (pin "16") (pinfunction "16_16") (pintype "passive"))
      (node (ref "JP3") (pin "2") (pinfunction "2_2") (pintype "passive"))
    )
    (net (code "19") (name "Net-(J6-Pad13)") (class "Default")
      (node (ref "J6") (pin "13") (pinfunction "13_13") (pintype "passive"))
      (node (ref "J6") (pin "14") (pinfunction "14_14") (pintype "passive"))
      (node (ref "JP4") (pin "2") (pinfunction "2_2") (pintype "passive"))
    )
    (net (code "20") (name "Net-(J6-Pad15)") (class "Default")
      (node (ref "J6") (pin "15") (pinfunction "15_15") (pintype "passive"))
      (node (ref "J6") (pin "16") (pinfunction "16_16") (pintype "passive"))
      (node (ref "JP5") (pin "2") (pinfunction "2_2") (pintype "passive"))
    )
    (net (code "21") (name "Net-(J8-Pad13)") (class "Default")
      (node (ref "J8") (pin "13") (pinfunction "13_13") (pintype "passive"))
      (node (ref "J8") (pin "14") (pinfunction "14_14") (pintype "passive"))
      (node (ref "JP6") (pin "2") (pinfunction "2_2") (pintype "passive"))
    )
    (net (code "22") (name "Net-(J8-Pad15)") (class "Default")
      (node (ref "J8") (pin "15") (pinfunction "15_15") (pintype "passive"))
      (node (ref "J8") (pin "16") (pinfunction "16_16") (pintype "passive"))
      (node (ref "JP7") (pin "2") (pinfunction "2_2") (pintype "passive"))
    )
    (net (code "23") (name "Net-(J10-Pad13)") (class "Default")
      (node (ref "J10") (pin "13") (pinfunction "13_13") (pintype "passive"))
      (node (ref "J10") (pin "14") (pinfunction "14_14") (pintype "passive"))
      (node (ref "JP8") (pin "2") (pinfunction "2_2") (pintype "passive"))
    )
    (net (code "24") (name "Net-(J10-Pad15)") (class "Default")
      (node (ref "J10") (pin "15") (pinfunction "15_15") (pintype "passive"))
      (node (ref "J10") (pin "16") (pinfunction "16_16") (pintype "passive"))
      (node (ref "JP9") (pin "2") (pinfunction "2_2") (pintype "passive"))
    )
    (net (code "25") (name "Net-(J12-Pad13)") (class "Default")
      (node (ref "J12") (pin "13") (pinfunction "13_13") (pintype "passive"))
      (node (ref "J12") (pin "14") (pinfunction "14_14") (pintype "passive"))
      (node (ref "JP10") (pin "2") (pinfunction "2_2") (pintype "passive"))
    )
    (net (code "26") (name "Net-(J12-Pad15)") (class "Default")
      (node (ref "J12") (pin "15") (pinfunction "15_15") (pintype "passive"))
      (node (ref "J12") (pin "16") (pinfunction "16_16") (pintype "passive"))
      (node (ref "JP11") (pin "2") (pinfunction "2_2") (pintype "passive"))
    )
    (net (code "27") (name "Net-(J14-Pad13)") (class "Default")
      (node (ref "J14") (pin "13") (pinfunction "13_13") (pintype "passive"))
      (node (ref "J14") (pin "14") (pinfunction "14_14") (pintype "passive"))
      (node (ref "JP12") (pin "2") (pinfunction "2_2") (pintype "passive"))
    )
    (net (code "28") (name "Net-(J14-Pad15)") (class "Default")
      (node (ref "J14") (pin "15") (pinfunction "15_15") (pintype "passive"))
      (node (ref "J14") (pin "16") (pinfunction "16_16") (pintype "passive"))
      (node (ref "JP13") (pin "2") (pinfunction "2_2") (pintype "passive"))
    )
    (net (code "29") (name "Net-(J16-Pad13)") (class "Default")
      (node (ref "J16") (pin "13") (pinfunction "13_13") (pintype "passive"))
      (node (ref "J16") (pin "14") (pinfunction "14_14") (pintype "passive"))
      (node (ref "JP14") (pin "2") (pinfunction "2_2") (pintype "passive"))
    )
    (net (code "30") (name "Net-(J16-Pad15)") (class "Default")
      (node (ref "J16") (pin "15") (pinfunction "15_15") (pintype "passive"))
      (node (ref "J16") (pin "16") (pinfunction "16_16") (pintype "passive"))
      (node (ref "JP15") (pin "2") (pinfunction "2_2") (pintype "passive"))
    )
    (net (code "31") (name "Net-(J17-Pad13)") (class "Default")
      (node (ref "J17") (pin "13") (pinfunction "13_13") (pintype "passive"))
      (node (ref "J17") (pin "14") (pinfunction "14_14") (pintype "passive"))
      (node (ref "JP17") (pin "2") (pinfunction "2_2") (pintype "passive"))
    )
    (net (code "32") (name "Net-(J17-Pad15)") (class "Default")
      (node (ref "J17") (pin "15") (pinfunction "15_15") (pintype "passive"))
      (node (ref "J17") (pin "16") (pinfunction "16_16") (pintype "passive"))
      (node (ref "JP18") (pin "2") (pinfunction "2_2") (pintype "passive"))
    )
    (net (code "33") (name "Net-(J21-Pad13)") (class "Default")
      (node (ref "J21") (pin "13") (pinfunction "13_13") (pintype "passive"))
      (node (ref "J21") (pin "14") (pinfunction "14_14") (pintype "passive"))
      (node (ref "JP19") (pin "2") (pinfunction "2_2") (pintype "passive"))
    )
    (net (code "34") (name "Net-(J21-Pad15)") (class "Default")
      (node (ref "J21") (pin "15") (pinfunction "15_15") (pintype "passive"))
      (node (ref "J21") (pin "16") (pinfunction "16_16") (pintype "passive"))
      (node (ref "JP20") (pin "2") (pinfunction "2_2") (pintype "passive"))
    )
    (net (code "35") (name "Net-(J23-Pad13)") (class "Default")
      (node (ref "J23") (pin "13") (pinfunction "13_13") (pintype "passive"))
      (node (ref "J23") (pin "14") (pinfunction "14_14") (pintype "passive"))
      (node (ref "JP21") (pin "2") (pinfunction "2_2") (pintype "passive"))
    )
    (net (code "36") (name "Net-(J23-Pad15)") (class "Default")
      (node (ref "J23") (pin "15") (pinfunction "15_15") (pintype "passive"))
      (node (ref "J23") (pin "16") (pinfunction "16_16") (pintype "passive"))
      (node (ref "JP22") (pin "2") (pinfunction "2_2") (pintype "passive"))
    )
    (net (code "37") (name "Net-(J29-Pad13)") (class "Default")
      (node (ref "J29") (pin "13") (pinfunction "13_13") (pintype "passive"))
      (node (ref "J29") (pin "14") (pinfunction "14_14") (pintype "passive"))
      (node (ref "JP23") (pin "2") (pinfunction "2_2") (pintype "passive"))
    )
    (net (code "38") (name "Net-(J29-Pad15)") (class "Default")
      (node (ref "J29") (pin "15") (pinfunction "15_15") (pintype "passive"))
      (node (ref "J29") (pin "16") (pinfunction "16_16") (pintype "passive"))
      (node (ref "JP24") (pin "2") (pinfunction "2_2") (pintype "passive"))
    )
    (net (code "39") (name "Net-(J31-Pad13)") (class "Default")
      (node (ref "J31") (pin "13") (pinfunction "13_13") (pintype "passive"))
      (node (ref "J31") (pin "14") (pinfunction "14_14") (pintype "passive"))
      (node (ref "JP25") (pin "2") (pinfunction "2_2") (pintype "passive"))
    )
    (net (code "40") (name "Net-(J31-Pad15)") (class "Default")
      (node (ref "J31") (pin "15") (pinfunction "15_15") (pintype "passive"))
      (node (ref "J31") (pin "16") (pinfunction "16_16") (pintype "passive"))
      (node (ref "JP26") (pin "2") (pinfunction "2_2") (pintype "passive"))
    )
    (net (code "41") (name "Net-(J33-Pad13)") (class "Default")
      (node (ref "J33") (pin "13") (pinfunction "13_13") (pintype "passive"))
      (node (ref "J33") (pin "14") (pinfunction "14_14") (pintype "passive"))
      (node (ref "JP27") (pin "2") (pinfunction "2_2") (pintype "passive"))
    )
    (net (code "42") (name "Net-(J33-Pad15)") (class "Default")
      (node (ref "J33") (pin "15") (pinfunction "15_15") (pintype "passive"))
      (node (ref "J33") (pin "16") (pinfunction "16_16") (pintype "passive"))
      (node (ref "JP28") (pin "2") (pinfunction "2_2") (pintype "passive"))
    )
    (net (code "43") (name "Net-(J35-Pad13)") (class "Default")
      (node (ref "J35") (pin "13") (pinfunction "13_13") (pintype "passive"))
      (node (ref "J35") (pin "14") (pinfunction "14_14") (pintype "passive"))
      (node (ref "JP29") (pin "2") (pinfunction "2_2") (pintype "passive"))
    )
    (net (code "44") (name "Net-(J35-Pad15)") (class "Default")
      (node (ref "J35") (pin "15") (pinfunction "15_15") (pintype "passive"))
      (node (ref "J35") (pin "16") (pinfunction "16_16") (pintype "passive"))
      (node (ref "JP30") (pin "2") (pinfunction "2_2") (pintype "passive"))
    )
    (net (code "45") (name "Net-(J37-Pad13)") (class "Default")
      (node (ref "J37") (pin "13") (pinfunction "13_13") (pintype "passive"))
      (node (ref "J37") (pin "14") (pinfunction "14_14") (pintype "passive"))
      (node (ref "JP31") (pin "2") (pinfunction "2_2") (pintype "passive"))
    )
    (net (code "46") (name "Net-(J37-Pad15)") (class "Default")
      (node (ref "J37") (pin "15") (pinfunction "15_15") (pintype "passive"))
      (node (ref "J37") (pin "16") (pinfunction "16_16") (pintype "passive"))
      (node (ref "JP32") (pin "2") (pinfunction "2_2") (pintype "passive"))
    )
  )
)
